# picWAVE.net
KiCad netlist of a schematic drawn in EAGLE
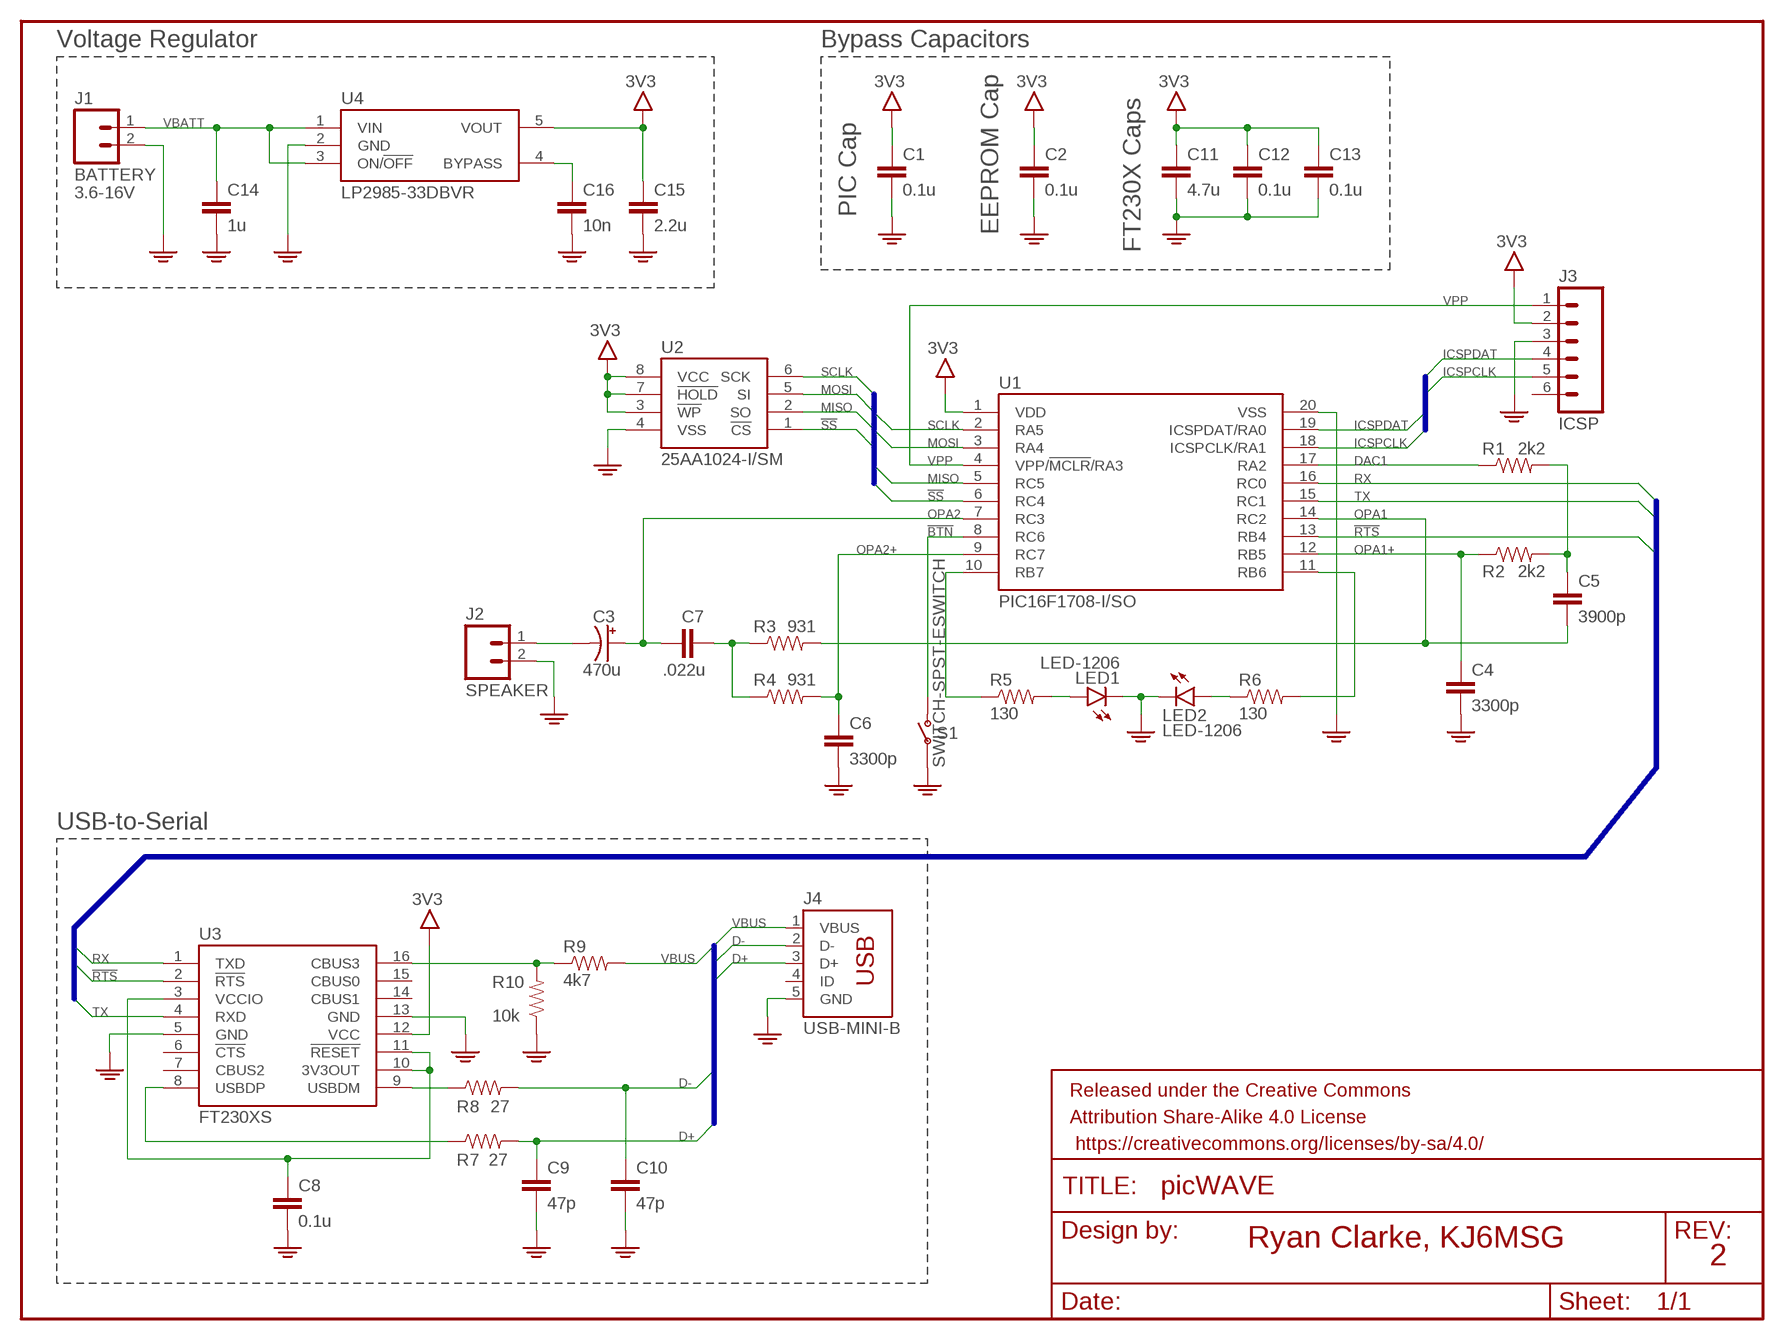
[diagram p0: schematic, sheet 1]

(export (version "E")
  (design (tool "Eeschema 10.0.6"))
  (components
    (comp (ref "C1")
      (value "0.1u")
      (footprint "eagle-import:1206")
      (libsource (lib "eagle-import") (part "CAPACITOR-1206"))
    )
    (comp (ref "C2")
      (value "0.1u")
      (footprint "eagle-import:1206")
      (libsource (lib "eagle-import") (part "CAPACITOR-1206"))
    )
    (comp (ref "C3")
      (value "470u")
      (footprint "eagle-import:NL1GS")
      (libsource (lib "eagle-import") (part "CAPACITOR-POL-NL1GS"))
    )
    (comp (ref "C4")
      (value "3300p")
      (footprint "eagle-import:1206")
      (libsource (lib "eagle-import") (part "CAPACITOR-1206"))
    )
    (comp (ref "C5")
      (value "3900p")
      (footprint "eagle-import:1206")
      (libsource (lib "eagle-import") (part "CAPACITOR-1206"))
    )
    (comp (ref "C6")
      (value "3300p")
      (footprint "eagle-import:1206")
      (libsource (lib "eagle-import") (part "CAPACITOR-1206"))
    )
    (comp (ref "C7")
      (value ".022u")
      (footprint "eagle-import:1206")
      (libsource (lib "eagle-import") (part "CAPACITOR-1206"))
    )
    (comp (ref "C8")
      (value "0.1u")
      (footprint "eagle-import:1206@1")
      (libsource (lib "eagle-import") (part "CAP1206"))
    )
    (comp (ref "C9")
      (value "47p")
      (footprint "eagle-import:1206@1")
      (libsource (lib "eagle-import") (part "CAP1206"))
    )
    (comp (ref "C10")
      (value "47p")
      (footprint "eagle-import:1206@1")
      (libsource (lib "eagle-import") (part "CAP1206"))
    )
    (comp (ref "C11")
      (value "4.7u")
      (footprint "eagle-import:1206@1")
      (libsource (lib "eagle-import") (part "CAP1206"))
    )
    (comp (ref "C12")
      (value "0.1u")
      (footprint "eagle-import:1206@1")
      (libsource (lib "eagle-import") (part "CAP1206"))
    )
    (comp (ref "C13")
      (value "0.1u")
      (footprint "eagle-import:1206@1")
      (libsource (lib "eagle-import") (part "CAP1206"))
    )
    (comp (ref "C14")
      (value "1u")
      (footprint "eagle-import:1206")
      (libsource (lib "eagle-import") (part "CAPACITOR-1206"))
    )
    (comp (ref "C15")
      (value "2.2u")
      (footprint "eagle-import:1206")
      (libsource (lib "eagle-import") (part "CAPACITOR-1206"))
    )
    (comp (ref "C16")
      (value "10n")
      (footprint "eagle-import:1206")
      (libsource (lib "eagle-import") (part "CAPACITOR-1206"))
    )
    (comp (ref "FRAME1")
      (value "FRAME-LETTERNO_PACKAGE")
      (footprint "eagle-import:DUMMY")
      (fields (field (name "DESIGNER") "Nobody"))
      (libsource (lib "eagle-import") (part "FRAME-LETTERNO_PACKAGE"))
    )
    (comp (ref "J1")
      (value "BATTERY")
      (footprint "eagle-import:22-05-3021")
      (fields (field (name "MANUFACTURER") "Molex"))
      (libsource (lib "eagle-import") (part "M02-MOLEX"))
    )
    (comp (ref "J2")
      (value "SPEAKER")
      (footprint "eagle-import:22-05-3021")
      (fields (field (name "MANUFACTURER") "Molex"))
      (libsource (lib "eagle-import") (part "M02-MOLEX"))
    )
    (comp (ref "J3")
      (value "ICSP")
      (footprint "eagle-import:1X06")
      (libsource (lib "eagle-import") (part "M06"))
    )
    (comp (ref "J4")
      (value "USB-MINI-B")
      (footprint "eagle-import:XM7D-0512")
      (libsource (lib "eagle-import") (part "USB-MINI-B-PTH"))
    )
    (comp (ref "LED1")
      (value "LED-1206")
      (footprint "eagle-import:LED-1206")
      (libsource (lib "eagle-import") (part "LED-1206"))
    )
    (comp (ref "LED2")
      (value "LED-1206")
      (footprint "eagle-import:LED-1206")
      (libsource (lib "eagle-import") (part "LED-1206"))
    )
    (comp (ref "R1")
      (value "2k2")
      (footprint "eagle-import:1206")
      (libsource (lib "eagle-import") (part "RESISTOR1206"))
    )
    (comp (ref "R2")
      (value "2k2")
      (footprint "eagle-import:1206")
      (libsource (lib "eagle-import") (part "RESISTOR1206"))
    )
    (comp (ref "R3")
      (value "931")
      (footprint "eagle-import:1206")
      (libsource (lib "eagle-import") (part "RESISTOR1206"))
    )
    (comp (ref "R4")
      (value "931")
      (footprint "eagle-import:1206")
      (libsource (lib "eagle-import") (part "RESISTOR1206"))
    )
    (comp (ref "R5")
      (value "130")
      (footprint "eagle-import:1206")
      (libsource (lib "eagle-import") (part "RESISTOR1206"))
    )
    (comp (ref "R6")
      (value "130")
      (footprint "eagle-import:1206")
      (libsource (lib "eagle-import") (part "RESISTOR1206"))
    )
    (comp (ref "R7")
      (value "27")
      (footprint "eagle-import:1206")
      (libsource (lib "eagle-import") (part "RESISTOR1206"))
    )
    (comp (ref "R8")
      (value "27")
      (footprint "eagle-import:1206")
      (libsource (lib "eagle-import") (part "RESISTOR1206"))
    )
    (comp (ref "R9")
      (value "4k7")
      (footprint "eagle-import:1206")
      (libsource (lib "eagle-import") (part "RESISTOR1206"))
    )
    (comp (ref "R10")
      (value "10k")
      (footprint "eagle-import:1206")
      (libsource (lib "eagle-import") (part "RESISTOR1206"))
    )
    (comp (ref "S1")
      (value "SWITCH-SPST-ESWITCH")
      (footprint "eagle-import:KS-00Q-01")
      (fields (field (name "MANUFACTURER") "E-Switch"))
      (libsource (lib "eagle-import") (part "SWITCH-SPST-ESWITCH"))
    )
    (comp (ref "U1")
      (value "PIC16F1708-I/SO")
      (footprint "eagle-import:SOIC-20-W")
      (libsource (lib "eagle-import") (part "PIC16F1708-/SOI"))
    )
    (comp (ref "U2")
      (value "25AA1024-I/SM")
      (footprint "eagle-import:SOIJ-8")
      (libsource (lib "eagle-import") (part "25AA1024-I/SM"))
    )
    (comp (ref "U3")
      (value "FT230XS")
      (footprint "eagle-import:SSOP-16")
      (libsource (lib "eagle-import") (part "FT230XS"))
    )
    (comp (ref "U4")
      (value "LP2985-33DBVR")
      (footprint "eagle-import:SOT-23-5")
      (libsource (lib "eagle-import") (part "LP2985"))
    )
  )
  (nets
    (net (code "1") (name "/D+") (class "Default")
      (node (ref "C9") (pin "1") (pinfunction "1_1") (pintype "passive"))
      (node (ref "J4") (pin "3") (pinfunction "D+_3") (pintype "bidirectional"))
      (node (ref "R7") (pin "2") (pinfunction "2_2") (pintype "passive"))
    )
    (net (code "2") (name "/D-") (class "Default")
      (node (ref "C10") (pin "1") (pinfunction "1_1") (pintype "passive"))
      (node (ref "J4") (pin "2") (pinfunction "D-_2") (pintype "bidirectional"))
      (node (ref "R8") (pin "2") (pinfunction "2_2") (pintype "passive"))
    )
    (net (code "3") (name "/DAC1") (class "Default")
      (node (ref "R1") (pin "1") (pinfunction "1_1") (pintype "passive"))
      (node (ref "U1") (pin "17") (pinfunction "RA2_17") (pintype "bidirectional"))
    )
    (net (code "4") (name "/ICSPCLK") (class "Default")
      (node (ref "J3") (pin "5") (pinfunction "5_5") (pintype "passive"))
      (node (ref "U1") (pin "18") (pinfunction "ICSPCLK/RA1_18") (pintype "bidirectional"))
    )
    (net (code "5") (name "/ICSPDAT") (class "Default")
      (node (ref "J3") (pin "4") (pinfunction "4_4") (pintype "passive"))
      (node (ref "U1") (pin "19") (pinfunction "ICSPDAT/RA0_19") (pintype "bidirectional"))
    )
    (net (code "6") (name "/MISO") (class "Default")
      (node (ref "U1") (pin "5") (pinfunction "RC5_5") (pintype "bidirectional"))
      (node (ref "U2") (pin "2") (pinfunction "SO_2") (pintype "bidirectional"))
    )
    (net (code "7") (name "/MOSI") (class "Default")
      (node (ref "U1") (pin "3") (pinfunction "RA4_3") (pintype "bidirectional"))
      (node (ref "U2") (pin "5") (pinfunction "SI_5") (pintype "bidirectional"))
    )
    (net (code "8") (name "/OPA1") (class "Default")
      (node (ref "C5") (pin "2") (pinfunction "2_2") (pintype "passive"))
      (node (ref "R3") (pin "2") (pinfunction "2_2") (pintype "passive"))
      (node (ref "U1") (pin "14") (pinfunction "RC2_14") (pintype "bidirectional"))
    )
    (net (code "9") (name "/OPA1+") (class "Default")
      (node (ref "C4") (pin "1") (pinfunction "1_1") (pintype "passive"))
      (node (ref "R2") (pin "1") (pinfunction "1_1") (pintype "passive"))
      (node (ref "U1") (pin "12") (pinfunction "RB5_12") (pintype "bidirectional"))
    )
    (net (code "10") (name "/OPA2") (class "Default")
      (node (ref "C3") (pin "+") (pinfunction "+_+") (pintype "passive"))
      (node (ref "C7") (pin "2") (pinfunction "2_2") (pintype "passive"))
      (node (ref "U1") (pin "7") (pinfunction "RC3_7") (pintype "bidirectional"))
    )
    (net (code "11") (name "/OPA2+") (class "Default")
      (node (ref "C6") (pin "1") (pinfunction "1_1") (pintype "passive"))
      (node (ref "R4") (pin "2") (pinfunction "2_2") (pintype "passive"))
      (node (ref "U1") (pin "9") (pinfunction "RC7_9") (pintype "bidirectional"))
    )
    (net (code "12") (name "/RX") (class "Default")
      (node (ref "U1") (pin "16") (pinfunction "RC0_16") (pintype "bidirectional"))
      (node (ref "U3") (pin "1") (pinfunction "TXD_1") (pintype "bidirectional"))
    )
    (net (code "13") (name "/SCLK") (class "Default")
      (node (ref "U1") (pin "2") (pinfunction "RA5_2") (pintype "bidirectional"))
      (node (ref "U2") (pin "6") (pinfunction "SCK_6") (pintype "bidirectional"))
    )
    (net (code "14") (name "/TX") (class "Default")
      (node (ref "U1") (pin "15") (pinfunction "RC1_15") (pintype "bidirectional"))
      (node (ref "U3") (pin "4") (pinfunction "RXD_4") (pintype "bidirectional"))
    )
    (net (code "15") (name "/VBATT") (class "Default")
      (node (ref "C14") (pin "1") (pinfunction "1_1") (pintype "passive"))
      (node (ref "J1") (pin "1") (pinfunction "1_1") (pintype "passive"))
      (node (ref "U4") (pin "1") (pinfunction "VIN_1") (pintype "bidirectional"))
      (node (ref "U4") (pin "3") (pinfunction "ON/~{OFF}_3") (pintype "bidirectional"))
    )
    (net (code "16") (name "/VBUS") (class "Default")
      (node (ref "J4") (pin "1") (pinfunction "VBUS_1") (pintype "bidirectional"))
      (node (ref "R9") (pin "2") (pinfunction "2_2") (pintype "passive"))
    )
    (net (code "17") (name "/VPP") (class "Default")
      (node (ref "J3") (pin "1") (pinfunction "1_1") (pintype "passive"))
      (node (ref "U1") (pin "4") (pinfunction "VPP/~{MCLR}/RA3_4") (pintype "input"))
    )
    (net (code "18") (name "/~{BTN}") (class "Default")
      (node (ref "S1") (pin "2") (pinfunction "2_2") (pintype "passive"))
      (node (ref "S1") (pin "4") (pinfunction "2_4") (pintype "passive"))
      (node (ref "U1") (pin "8") (pinfunction "RC6_8") (pintype "bidirectional"))
    )
    (net (code "19") (name "/~{RTS}") (class "Default")
      (node (ref "U1") (pin "13") (pinfunction "RB4_13") (pintype "bidirectional"))
      (node (ref "U3") (pin "2") (pinfunction "~{RTS}_2") (pintype "bidirectional"))
    )
    (net (code "20") (name "/~{SS}") (class "Default")
      (node (ref "U1") (pin "6") (pinfunction "RC4_6") (pintype "bidirectional"))
      (node (ref "U2") (pin "1") (pinfunction "~{CS}_1") (pintype "bidirectional"))
    )
    (net (code "21") (name "3V3") (class "Default")
      (node (ref "C1") (pin "1") (pinfunction "1_1") (pintype "passive"))
      (node (ref "C11") (pin "1") (pinfunction "1_1") (pintype "passive"))
      (node (ref "C12") (pin "1") (pinfunction "1_1") (pintype "passive"))
      (node (ref "C13") (pin "1") (pinfunction "1_1") (pintype "passive"))
      (node (ref "C15") (pin "1") (pinfunction "1_1") (pintype "passive"))
      (node (ref "C2") (pin "1") (pinfunction "1_1") (pintype "passive"))
      (node (ref "J3") (pin "2") (pinfunction "2_2") (pintype "passive"))
      (node (ref "U1") (pin "1") (pinfunction "VDD_1") (pintype "bidirectional"))
      (node (ref "U2") (pin "3") (pinfunction "~{WP}_3") (pintype "bidirectional"))
      (node (ref "U2") (pin "7") (pinfunction "~{HOLD}_7") (pintype "bidirectional"))
      (node (ref "U2") (pin "8") (pinfunction "VCC_8") (pintype "bidirectional"))
      (node (ref "U3") (pin "12") (pinfunction "VCC_12") (pintype "bidirectional"))
      (node (ref "U4") (pin "5") (pinfunction "VOUT_5") (pintype "bidirectional"))
    )
    (net (code "22") (name "GND") (class "Default")
      (node (ref "C1") (pin "2") (pinfunction "2_2") (pintype "passive"))
      (node (ref "C10") (pin "2") (pinfunction "2_2") (pintype "passive"))
      (node (ref "C11") (pin "2") (pinfunction "2_2") (pintype "passive"))
      (node (ref "C12") (pin "2") (pinfunction "2_2") (pintype "passive"))
      (node (ref "C13") (pin "2") (pinfunction "2_2") (pintype "passive"))
      (node (ref "C14") (pin "2") (pinfunction "2_2") (pintype "passive"))
      (node (ref "C15") (pin "2") (pinfunction "2_2") (pintype "passive"))
      (node (ref "C16") (pin "2") (pinfunction "2_2") (pintype "passive"))
      (node (ref "C2") (pin "2") (pinfunction "2_2") (pintype "passive"))
      (node (ref "C4") (pin "2") (pinfunction "2_2") (pintype "passive"))
      (node (ref "C6") (pin "2") (pinfunction "2_2") (pintype "passive"))
      (node (ref "C8") (pin "2") (pinfunction "2_2") (pintype "passive"))
      (node (ref "C9") (pin "2") (pinfunction "2_2") (pintype "passive"))
      (node (ref "J1") (pin "2") (pinfunction "2_2") (pintype "passive"))
      (node (ref "J2") (pin "2") (pinfunction "2_2") (pintype "passive"))
      (node (ref "J3") (pin "3") (pinfunction "3_3") (pintype "passive"))
      (node (ref "J4") (pin "5") (pinfunction "GND_5") (pintype "bidirectional"))
      (node (ref "LED1") (pin "C") (pinfunction "C_C") (pintype "passive"))
      (node (ref "LED2") (pin "C") (pinfunction "C_C") (pintype "passive"))
      (node (ref "R10") (pin "1") (pinfunction "1_1") (pintype "passive"))
      (node (ref "S1") (pin "1") (pinfunction "1_1") (pintype "passive"))
      (node (ref "S1") (pin "3") (pinfunction "1_3") (pintype "passive"))
      (node (ref "U1") (pin "20") (pinfunction "VSS_20") (pintype "bidirectional"))
      (node (ref "U2") (pin "4") (pinfunction "VSS_4") (pintype "bidirectional"))
      (node (ref "U3") (pin "13") (pinfunction "GND_13") (pintype "bidirectional"))
      (node (ref "U3") (pin "5") (pinfunction "GND_5") (pintype "bidirectional"))
      (node (ref "U4") (pin "2") (pinfunction "GND_2") (pintype "bidirectional"))
    )
    (net (code "23") (name "Net-(C3-Pad-)") (class "Default")
      (node (ref "C3") (pin "-") (pinfunction "-_-") (pintype "passive"))
      (node (ref "J2") (pin "1") (pinfunction "1_1") (pintype "passive"))
    )
    (net (code "24") (name "Net-(C5-Pad1)") (class "Default")
      (node (ref "C5") (pin "1") (pinfunction "1_1") (pintype "passive"))
      (node (ref "R1") (pin "2") (pinfunction "2_2") (pintype "passive"))
      (node (ref "R2") (pin "2") (pinfunction "2_2") (pintype "passive"))
    )
    (net (code "25") (name "Net-(C7-Pad1)") (class "Default")
      (node (ref "C7") (pin "1") (pinfunction "1_1") (pintype "passive"))
      (node (ref "R3") (pin "1") (pinfunction "1_1") (pintype "passive"))
      (node (ref "R4") (pin "1") (pinfunction "1_1") (pintype "passive"))
    )
    (net (code "26") (name "Net-(LED1-PadA)") (class "Default")
      (node (ref "LED1") (pin "A") (pinfunction "A_A") (pintype "passive"))
      (node (ref "R5") (pin "2") (pinfunction "2_2") (pintype "passive"))
    )
    (net (code "27") (name "Net-(LED2-PadA)") (class "Default")
      (node (ref "LED2") (pin "A") (pinfunction "A_A") (pintype "passive"))
      (node (ref "R6") (pin "1") (pinfunction "1_1") (pintype "passive"))
    )
    (net (code "28") (name "Net-(U1-RB6)") (class "Default")
      (node (ref "R6") (pin "2") (pinfunction "2_2") (pintype "passive"))
      (node (ref "U1") (pin "11") (pinfunction "RB6_11") (pintype "bidirectional"))
    )
    (net (code "29") (name "Net-(U1-RB7)") (class "Default")
      (node (ref "R5") (pin "1") (pinfunction "1_1") (pintype "passive"))
      (node (ref "U1") (pin "10") (pinfunction "RB7_10") (pintype "bidirectional"))
    )
    (net (code "30") (name "Net-(U3-3V3OUT)") (class "Default")
      (node (ref "C8") (pin "1") (pinfunction "1_1") (pintype "passive"))
      (node (ref "U3") (pin "10") (pinfunction "3V3OUT_10") (pintype "bidirectional"))
      (node (ref "U3") (pin "11") (pinfunction "~{RESET}_11") (pintype "bidirectional"))
      (node (ref "U3") (pin "3") (pinfunction "VCCIO_3") (pintype "bidirectional"))
    )
    (net (code "31") (name "Net-(U3-CBUS3)") (class "Default")
      (node (ref "R10") (pin "2") (pinfunction "2_2") (pintype "passive"))
      (node (ref "R9") (pin "1") (pinfunction "1_1") (pintype "passive"))
      (node (ref "U3") (pin "16") (pinfunction "CBUS3_16") (pintype "bidirectional"))
    )
    (net (code "32") (name "Net-(U3-USBDM)") (class "Default")
      (node (ref "R8") (pin "1") (pinfunction "1_1") (pintype "passive"))
      (node (ref "U3") (pin "9") (pinfunction "USBDM_9") (pintype "bidirectional"))
    )
    (net (code "33") (name "Net-(U3-USBDP)") (class "Default")
      (node (ref "R7") (pin "1") (pinfunction "1_1") (pintype "passive"))
      (node (ref "U3") (pin "8") (pinfunction "USBDP_8") (pintype "bidirectional"))
    )
    (net (code "34") (name "Net-(U4-BYPASS)") (class "Default")
      (node (ref "C16") (pin "1") (pinfunction "1_1") (pintype "passive"))
      (node (ref "U4") (pin "4") (pinfunction "BYPASS_4") (pintype "bidirectional"))
    )
    (net (code "35") (name "unconnected-(J3-Pad6)") (class "Default")
      (node (ref "J3") (pin "6") (pinfunction "6_6") (pintype "passive"))
    )
    (net (code "36") (name "unconnected-(J4-ID-Pad4)") (class "Default")
      (node (ref "J4") (pin "4") (pinfunction "ID_4") (pintype "bidirectional"))
    )
    (net (code "37") (name "unconnected-(U3-CBUS0-Pad15)") (class "Default")
      (node (ref "U3") (pin "15") (pinfunction "CBUS0_15") (pintype "bidirectional"))
    )
    (net (code "38") (name "unconnected-(U3-CBUS1-Pad14)") (class "Default")
      (node (ref "U3") (pin "14") (pinfunction "CBUS1_14") (pintype "bidirectional"))
    )
    (net (code "39") (name "unconnected-(U3-CBUS2-Pad7)") (class "Default")
      (node (ref "U3") (pin "7") (pinfunction "CBUS2_7") (pintype "bidirectional"))
    )
    (net (code "40") (name "unconnected-(U3-~{CTS}-Pad6)") (class "Default")
      (node (ref "U3") (pin "6") (pinfunction "~{CTS}_6") (pintype "bidirectional"))
    )
  )
)
